# GPduinoWiFi.net
KiCad netlist of a schematic drawn in EAGLE
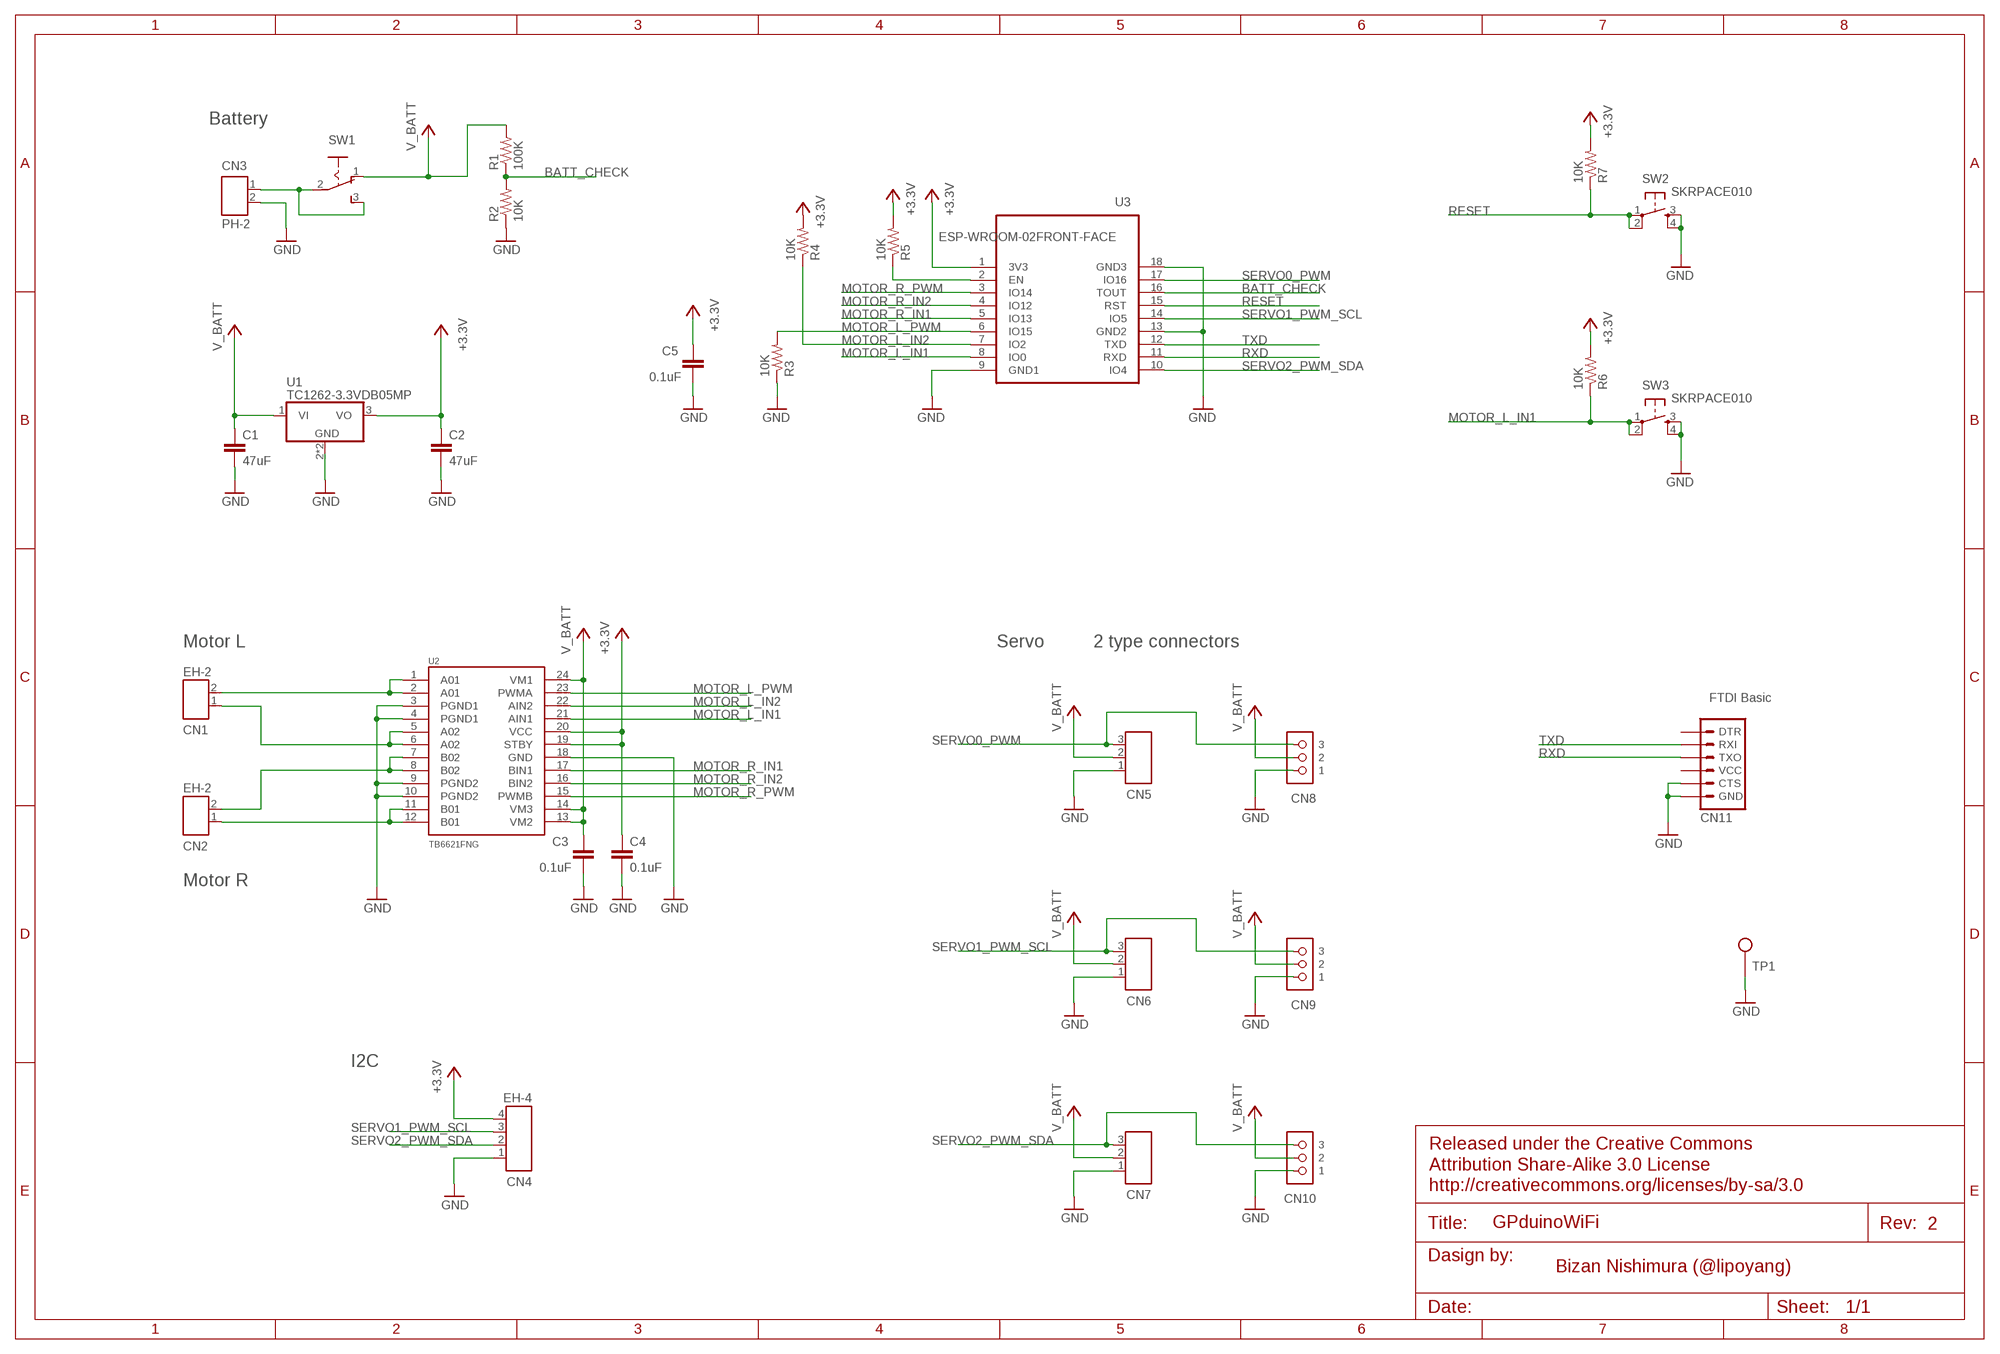
[diagram p0: schematic, sheet 1]

(export (version "E")
  (design (tool "Eeschema 10.0.6"))
  (components
    (comp (ref "C1")
      (value "47uF")
      (footprint "eagle-import:C3216")
      (libsource (lib "eagle-import") (part "C-EUC3216"))
    )
    (comp (ref "C2")
      (value "47uF")
      (footprint "eagle-import:C3216")
      (libsource (lib "eagle-import") (part "C-EUC3216"))
    )
    (comp (ref "C3")
      (value "0.1uF")
      (footprint "eagle-import:C1608")
      (libsource (lib "eagle-import") (part "C-EUC1608"))
    )
    (comp (ref "C4")
      (value "0.1uF")
      (footprint "eagle-import:C1608")
      (libsource (lib "eagle-import") (part "C-EUC1608"))
    )
    (comp (ref "C5")
      (value "0.1uF")
      (footprint "eagle-import:C1608")
      (libsource (lib "eagle-import") (part "C-EUC1608"))
    )
    (comp (ref "CN1")
      (value "EH-2")
      (footprint "eagle-import:EH-2")
      (libsource (lib "eagle-import") (part "EH-2"))
    )
    (comp (ref "CN2")
      (value "EH-2")
      (footprint "eagle-import:EH-2")
      (libsource (lib "eagle-import") (part "EH-2"))
    )
    (comp (ref "CN3")
      (value "PH-2")
      (footprint "eagle-import:PH-2")
      (libsource (lib "eagle-import") (part "PH-2"))
    )
    (comp (ref "CN4")
      (value "EH-4")
      (footprint "eagle-import:EH-4")
      (libsource (lib "eagle-import") (part "EH-4"))
    )
    (comp (ref "CN5")
      (value "PICOBLADE-3")
      (footprint "eagle-import:PICOBLADE-3")
      (libsource (lib "eagle-import") (part "PICOBLADE-3"))
    )
    (comp (ref "CN6")
      (value "PICOBLADE-3")
      (footprint "eagle-import:PICOBLADE-3")
      (libsource (lib "eagle-import") (part "PICOBLADE-3"))
    )
    (comp (ref "CN7")
      (value "PICOBLADE-3")
      (footprint "eagle-import:PICOBLADE-3")
      (libsource (lib "eagle-import") (part "PICOBLADE-3"))
    )
    (comp (ref "CN8")
      (value "cn6")
      (footprint "eagle-import:CON_RC_SERVO")
      (libsource (lib "eagle-import") (part "PINHD-1X3"))
    )
    (comp (ref "CN9")
      (value "cn6")
      (footprint "eagle-import:CON_RC_SERVO")
      (libsource (lib "eagle-import") (part "PINHD-1X3"))
    )
    (comp (ref "CN10")
      (value "cn6")
      (footprint "eagle-import:CON_RC_SERVO")
      (libsource (lib "eagle-import") (part "PINHD-1X3"))
    )
    (comp (ref "CN11")
      (value "FTDI Basic")
      (footprint "eagle-import:1X06")
      (libsource (lib "eagle-import") (part "ARDUINO_SERIAL_PROGRAMPTH"))
    )
    (comp (ref "R1")
      (value "100K")
      (footprint "eagle-import:0603-RES")
      (libsource (lib "eagle-import") (part "RESISTOR0603-RES"))
    )
    (comp (ref "R2")
      (value "10K")
      (footprint "eagle-import:0603-RES")
      (libsource (lib "eagle-import") (part "RESISTOR0603-RES"))
    )
    (comp (ref "R3")
      (value "10K")
      (footprint "eagle-import:0603-RES")
      (libsource (lib "eagle-import") (part "RESISTOR0603-RES"))
    )
    (comp (ref "R4")
      (value "10K")
      (footprint "eagle-import:0603-RES")
      (libsource (lib "eagle-import") (part "RESISTOR0603-RES"))
    )
    (comp (ref "R5")
      (value "10K")
      (footprint "eagle-import:0603-RES")
      (libsource (lib "eagle-import") (part "RESISTOR0603-RES"))
    )
    (comp (ref "R6")
      (value "10K")
      (footprint "eagle-import:0603-RES")
      (libsource (lib "eagle-import") (part "RESISTOR0603-RES"))
    )
    (comp (ref "R7")
      (value "10K")
      (footprint "eagle-import:0603-RES")
      (libsource (lib "eagle-import") (part "RESISTOR0603-RES"))
    )
    (comp (ref "SW1")
      (value "SW1")
      (footprint "eagle-import:SLIDE-SW")
      (libsource (lib "eagle-import") (part "M251"))
    )
    (comp (ref "SW2")
      (value "SKRPACE010")
      (footprint "eagle-import:SKRPACE010")
      (libsource (lib "eagle-import") (part "SKRPACE010"))
    )
    (comp (ref "SW3")
      (value "SKRPACE010")
      (footprint "eagle-import:SKRPACE010")
      (libsource (lib "eagle-import") (part "SKRPACE010"))
    )
    (comp (ref "TP1")
      (value "TEST_PIN")
      (footprint "eagle-import:TEST_PIN")
      (libsource (lib "eagle-import") (part "TEST_PIN"))
    )
    (comp (ref "U1")
      (value "TC1262-3.3VDB05MP")
      (footprint "eagle-import:SOT223")
      (libsource (lib "eagle-import") (part "TC1262-3.3VDBMP05"))
    )
    (comp (ref "U2")
      (value "TB6621FNG")
      (footprint "eagle-import:SSOP24")
      (libsource (lib "eagle-import") (part "TB6621FNG"))
    )
    (comp (ref "U3")
      (value "ESP-WROOM-02FRONT-FACE")
      (footprint "eagle-import:FRONT-FACE")
      (libsource (lib "eagle-import") (part "ESP-WROOM-02FRONT-FACE"))
    )
  )
  (nets
    (net (code "1") (name "+3.3V") (class "Default")
      (node (ref "C2") (pin "1") (pinfunction "1_1") (pintype "passive"))
      (node (ref "C4") (pin "1") (pinfunction "1_1") (pintype "passive"))
      (node (ref "C5") (pin "1") (pinfunction "1_1") (pintype "passive"))
      (node (ref "CN4") (pin "4") (pinfunction "4_4") (pintype "bidirectional"))
      (node (ref "R4") (pin "2") (pinfunction "2_2") (pintype "passive"))
      (node (ref "R5") (pin "2") (pinfunction "2_2") (pintype "passive"))
      (node (ref "R6") (pin "2") (pinfunction "2_2") (pintype "passive"))
      (node (ref "R7") (pin "2") (pinfunction "2_2") (pintype "passive"))
      (node (ref "U1") (pin "3") (pinfunction "VO_3") (pintype "passive"))
      (node (ref "U2") (pin "19") (pinfunction "STBY_19") (pintype "bidirectional"))
      (node (ref "U2") (pin "20") (pinfunction "VCC_20") (pintype "bidirectional"))
      (node (ref "U3") (pin "1") (pinfunction "3V3_1") (pintype "power_in"))
    )
    (net (code "2") (name "/BATT_CHECK") (class "Default")
      (node (ref "R1") (pin "1") (pinfunction "1_1") (pintype "passive"))
      (node (ref "R2") (pin "2") (pinfunction "2_2") (pintype "passive"))
      (node (ref "U3") (pin "16") (pinfunction "TOUT_16") (pintype "bidirectional"))
    )
    (net (code "3") (name "/MOTOR_L_IN1") (class "Default")
      (node (ref "R6") (pin "1") (pinfunction "1_1") (pintype "passive"))
      (node (ref "SW3") (pin "1") (pinfunction "1_1") (pintype "passive"))
      (node (ref "SW3") (pin "2") (pinfunction "2_2") (pintype "passive"))
      (node (ref "U2") (pin "21") (pinfunction "AIN1_21") (pintype "bidirectional"))
      (node (ref "U3") (pin "8") (pinfunction "IO0_8") (pintype "bidirectional"))
    )
    (net (code "4") (name "/MOTOR_L_IN2") (class "Default")
      (node (ref "R4") (pin "1") (pinfunction "1_1") (pintype "passive"))
      (node (ref "U2") (pin "22") (pinfunction "AIN2_22") (pintype "bidirectional"))
      (node (ref "U3") (pin "7") (pinfunction "IO2_7") (pintype "bidirectional"))
    )
    (net (code "5") (name "/MOTOR_L_PWM") (class "Default")
      (node (ref "R3") (pin "2") (pinfunction "2_2") (pintype "passive"))
      (node (ref "U2") (pin "23") (pinfunction "PWMA_23") (pintype "bidirectional"))
      (node (ref "U3") (pin "6") (pinfunction "IO15_6") (pintype "bidirectional"))
    )
    (net (code "6") (name "/MOTOR_R_IN1") (class "Default")
      (node (ref "U2") (pin "17") (pinfunction "BIN1_17") (pintype "bidirectional"))
      (node (ref "U3") (pin "5") (pinfunction "IO13_5") (pintype "bidirectional"))
    )
    (net (code "7") (name "/MOTOR_R_IN2") (class "Default")
      (node (ref "U2") (pin "16") (pinfunction "BIN2_16") (pintype "bidirectional"))
      (node (ref "U3") (pin "4") (pinfunction "IO12_4") (pintype "bidirectional"))
    )
    (net (code "8") (name "/MOTOR_R_PWM") (class "Default")
      (node (ref "U2") (pin "15") (pinfunction "PWMB_15") (pintype "bidirectional"))
      (node (ref "U3") (pin "3") (pinfunction "IO14_3") (pintype "bidirectional"))
    )
    (net (code "9") (name "/RESET") (class "Default")
      (node (ref "R7") (pin "1") (pinfunction "1_1") (pintype "passive"))
      (node (ref "SW2") (pin "1") (pinfunction "1_1") (pintype "passive"))
      (node (ref "SW2") (pin "2") (pinfunction "2_2") (pintype "passive"))
      (node (ref "U3") (pin "15") (pinfunction "RST_15") (pintype "bidirectional"))
    )
    (net (code "10") (name "/RXD") (class "Default")
      (node (ref "CN11") (pin "3") (pinfunction "TXO_3") (pintype "passive"))
      (node (ref "U3") (pin "11") (pinfunction "RXD_11") (pintype "bidirectional"))
    )
    (net (code "11") (name "/SERVO0_PWM") (class "Default")
      (node (ref "CN5") (pin "3") (pinfunction "3_3") (pintype "bidirectional"))
      (node (ref "CN8") (pin "3") (pinfunction "3_3") (pintype "passive"))
      (node (ref "U3") (pin "17") (pinfunction "IO16_17") (pintype "bidirectional"))
    )
    (net (code "12") (name "/SERVO1_PWM_SCL") (class "Default")
      (node (ref "CN4") (pin "3") (pinfunction "3_3") (pintype "bidirectional"))
      (node (ref "CN6") (pin "3") (pinfunction "3_3") (pintype "bidirectional"))
      (node (ref "CN9") (pin "3") (pinfunction "3_3") (pintype "passive"))
      (node (ref "U3") (pin "14") (pinfunction "IO5_14") (pintype "open_collector"))
    )
    (net (code "13") (name "/SERVO2_PWM_SDA") (class "Default")
      (node (ref "CN10") (pin "3") (pinfunction "3_3") (pintype "passive"))
      (node (ref "CN4") (pin "2") (pinfunction "2_2") (pintype "bidirectional"))
      (node (ref "CN7") (pin "3") (pinfunction "3_3") (pintype "bidirectional"))
      (node (ref "U3") (pin "10") (pinfunction "IO4_10") (pintype "bidirectional"))
    )
    (net (code "14") (name "/TXD") (class "Default")
      (node (ref "CN11") (pin "2") (pinfunction "RXI_2") (pintype "passive"))
      (node (ref "U3") (pin "12") (pinfunction "TXD_12") (pintype "bidirectional"))
    )
    (net (code "15") (name "GND") (class "Default")
      (node (ref "C1") (pin "2") (pinfunction "2_2") (pintype "passive"))
      (node (ref "C2") (pin "2") (pinfunction "2_2") (pintype "passive"))
      (node (ref "C3") (pin "2") (pinfunction "2_2") (pintype "passive"))
      (node (ref "C4") (pin "2") (pinfunction "2_2") (pintype "passive"))
      (node (ref "C5") (pin "2") (pinfunction "2_2") (pintype "passive"))
      (node (ref "CN10") (pin "1") (pinfunction "1_1") (pintype "passive"))
      (node (ref "CN11") (pin "5") (pinfunction "CTS_5") (pintype "passive"))
      (node (ref "CN11") (pin "6") (pinfunction "GND_6") (pintype "passive"))
      (node (ref "CN3") (pin "2") (pinfunction "2_2") (pintype "bidirectional"))
      (node (ref "CN4") (pin "1") (pinfunction "1_1") (pintype "bidirectional"))
      (node (ref "CN5") (pin "1") (pinfunction "1_1") (pintype "bidirectional"))
      (node (ref "CN6") (pin "1") (pinfunction "1_1") (pintype "bidirectional"))
      (node (ref "CN7") (pin "1") (pinfunction "1_1") (pintype "bidirectional"))
      (node (ref "CN8") (pin "1") (pinfunction "1_1") (pintype "passive"))
      (node (ref "CN9") (pin "1") (pinfunction "1_1") (pintype "passive"))
      (node (ref "R2") (pin "1") (pinfunction "1_1") (pintype "passive"))
      (node (ref "R3") (pin "1") (pinfunction "1_1") (pintype "passive"))
      (node (ref "SW2") (pin "3") (pinfunction "3_3") (pintype "passive"))
      (node (ref "SW2") (pin "4") (pinfunction "4_4") (pintype "passive"))
      (node (ref "SW3") (pin "3") (pinfunction "3_3") (pintype "passive"))
      (node (ref "SW3") (pin "4") (pinfunction "4_4") (pintype "passive"))
      (node (ref "TP1") (pin "1") (pinfunction "P$1_1") (pintype "bidirectional"))
      (node (ref "U1") (pin "2") (pinfunction "GND_2") (pintype "passive"))
      (node (ref "U1") (pin "4") (pinfunction "GND_4") (pintype "passive"))
      (node (ref "U2") (pin "10") (pinfunction "PGND2_10") (pintype "bidirectional"))
      (node (ref "U2") (pin "18") (pinfunction "GND_18") (pintype "bidirectional"))
      (node (ref "U2") (pin "3") (pinfunction "PGND1_3") (pintype "bidirectional"))
      (node (ref "U2") (pin "4") (pinfunction "PGND1_4") (pintype "bidirectional"))
      (node (ref "U2") (pin "9") (pinfunction "PGND2_9") (pintype "bidirectional"))
      (node (ref "U3") (pin "13") (pinfunction "GND2_13") (pintype "power_in"))
      (node (ref "U3") (pin "18") (pinfunction "GND3_18") (pintype "power_in"))
      (node (ref "U3") (pin "9") (pinfunction "GND1_9") (pintype "power_in"))
    )
    (net (code "16") (name "Net-(CN1-Pad1)") (class "Default")
      (node (ref "CN1") (pin "1") (pinfunction "1_1") (pintype "bidirectional"))
      (node (ref "U2") (pin "5") (pinfunction "A02_5") (pintype "bidirectional"))
      (node (ref "U2") (pin "6") (pinfunction "A02_6") (pintype "bidirectional"))
    )
    (net (code "17") (name "Net-(CN1-Pad2)") (class "Default")
      (node (ref "CN1") (pin "2") (pinfunction "2_2") (pintype "bidirectional"))
      (node (ref "U2") (pin "1") (pinfunction "A01_1") (pintype "bidirectional"))
      (node (ref "U2") (pin "2") (pinfunction "A01_2") (pintype "bidirectional"))
    )
    (net (code "18") (name "Net-(CN2-Pad1)") (class "Default")
      (node (ref "CN2") (pin "1") (pinfunction "1_1") (pintype "bidirectional"))
      (node (ref "U2") (pin "11") (pinfunction "B01_11") (pintype "bidirectional"))
      (node (ref "U2") (pin "12") (pinfunction "B01_12") (pintype "bidirectional"))
    )
    (net (code "19") (name "Net-(CN2-Pad2)") (class "Default")
      (node (ref "CN2") (pin "2") (pinfunction "2_2") (pintype "bidirectional"))
      (node (ref "U2") (pin "7") (pinfunction "B02_7") (pintype "bidirectional"))
      (node (ref "U2") (pin "8") (pinfunction "B02_8") (pintype "bidirectional"))
    )
    (net (code "20") (name "Net-(SW1-P)") (class "Default")
      (node (ref "CN3") (pin "1") (pinfunction "1_1") (pintype "bidirectional"))
      (node (ref "SW1") (pin "2") (pinfunction "P_2") (pintype "passive"))
      (node (ref "SW1") (pin "3") (pinfunction "S_3") (pintype "passive"))
    )
    (net (code "21") (name "Net-(U3-EN)") (class "Default")
      (node (ref "R5") (pin "1") (pinfunction "1_1") (pintype "passive"))
      (node (ref "U3") (pin "2") (pinfunction "EN_2") (pintype "bidirectional"))
    )
    (net (code "22") (name "V_BATT") (class "Default")
      (node (ref "C1") (pin "1") (pinfunction "1_1") (pintype "passive"))
      (node (ref "C3") (pin "1") (pinfunction "1_1") (pintype "passive"))
      (node (ref "CN10") (pin "2") (pinfunction "2_2") (pintype "passive"))
      (node (ref "CN5") (pin "2") (pinfunction "2_2") (pintype "bidirectional"))
      (node (ref "CN6") (pin "2") (pinfunction "2_2") (pintype "bidirectional"))
      (node (ref "CN7") (pin "2") (pinfunction "2_2") (pintype "bidirectional"))
      (node (ref "CN8") (pin "2") (pinfunction "2_2") (pintype "passive"))
      (node (ref "CN9") (pin "2") (pinfunction "2_2") (pintype "passive"))
      (node (ref "R1") (pin "2") (pinfunction "2_2") (pintype "passive"))
      (node (ref "SW1") (pin "1") (pinfunction "O_1") (pintype "passive"))
      (node (ref "U1") (pin "1") (pinfunction "VI_1") (pintype "input"))
      (node (ref "U2") (pin "13") (pinfunction "VM2_13") (pintype "bidirectional"))
      (node (ref "U2") (pin "14") (pinfunction "VM3_14") (pintype "bidirectional"))
      (node (ref "U2") (pin "24") (pinfunction "VM1_24") (pintype "bidirectional"))
    )
    (net (code "23") (name "unconnected-(CN11-DTR-Pad1)") (class "Default")
      (node (ref "CN11") (pin "1") (pinfunction "DTR_1") (pintype "passive"))
    )
    (net (code "24") (name "unconnected-(CN11-VCC-Pad4)") (class "Default")
      (node (ref "CN11") (pin "4") (pinfunction "VCC_4") (pintype "passive"))
    )
  )
)
